# LongLedPcb.net
KiCad netlist of a schematic drawn in Altium Designer
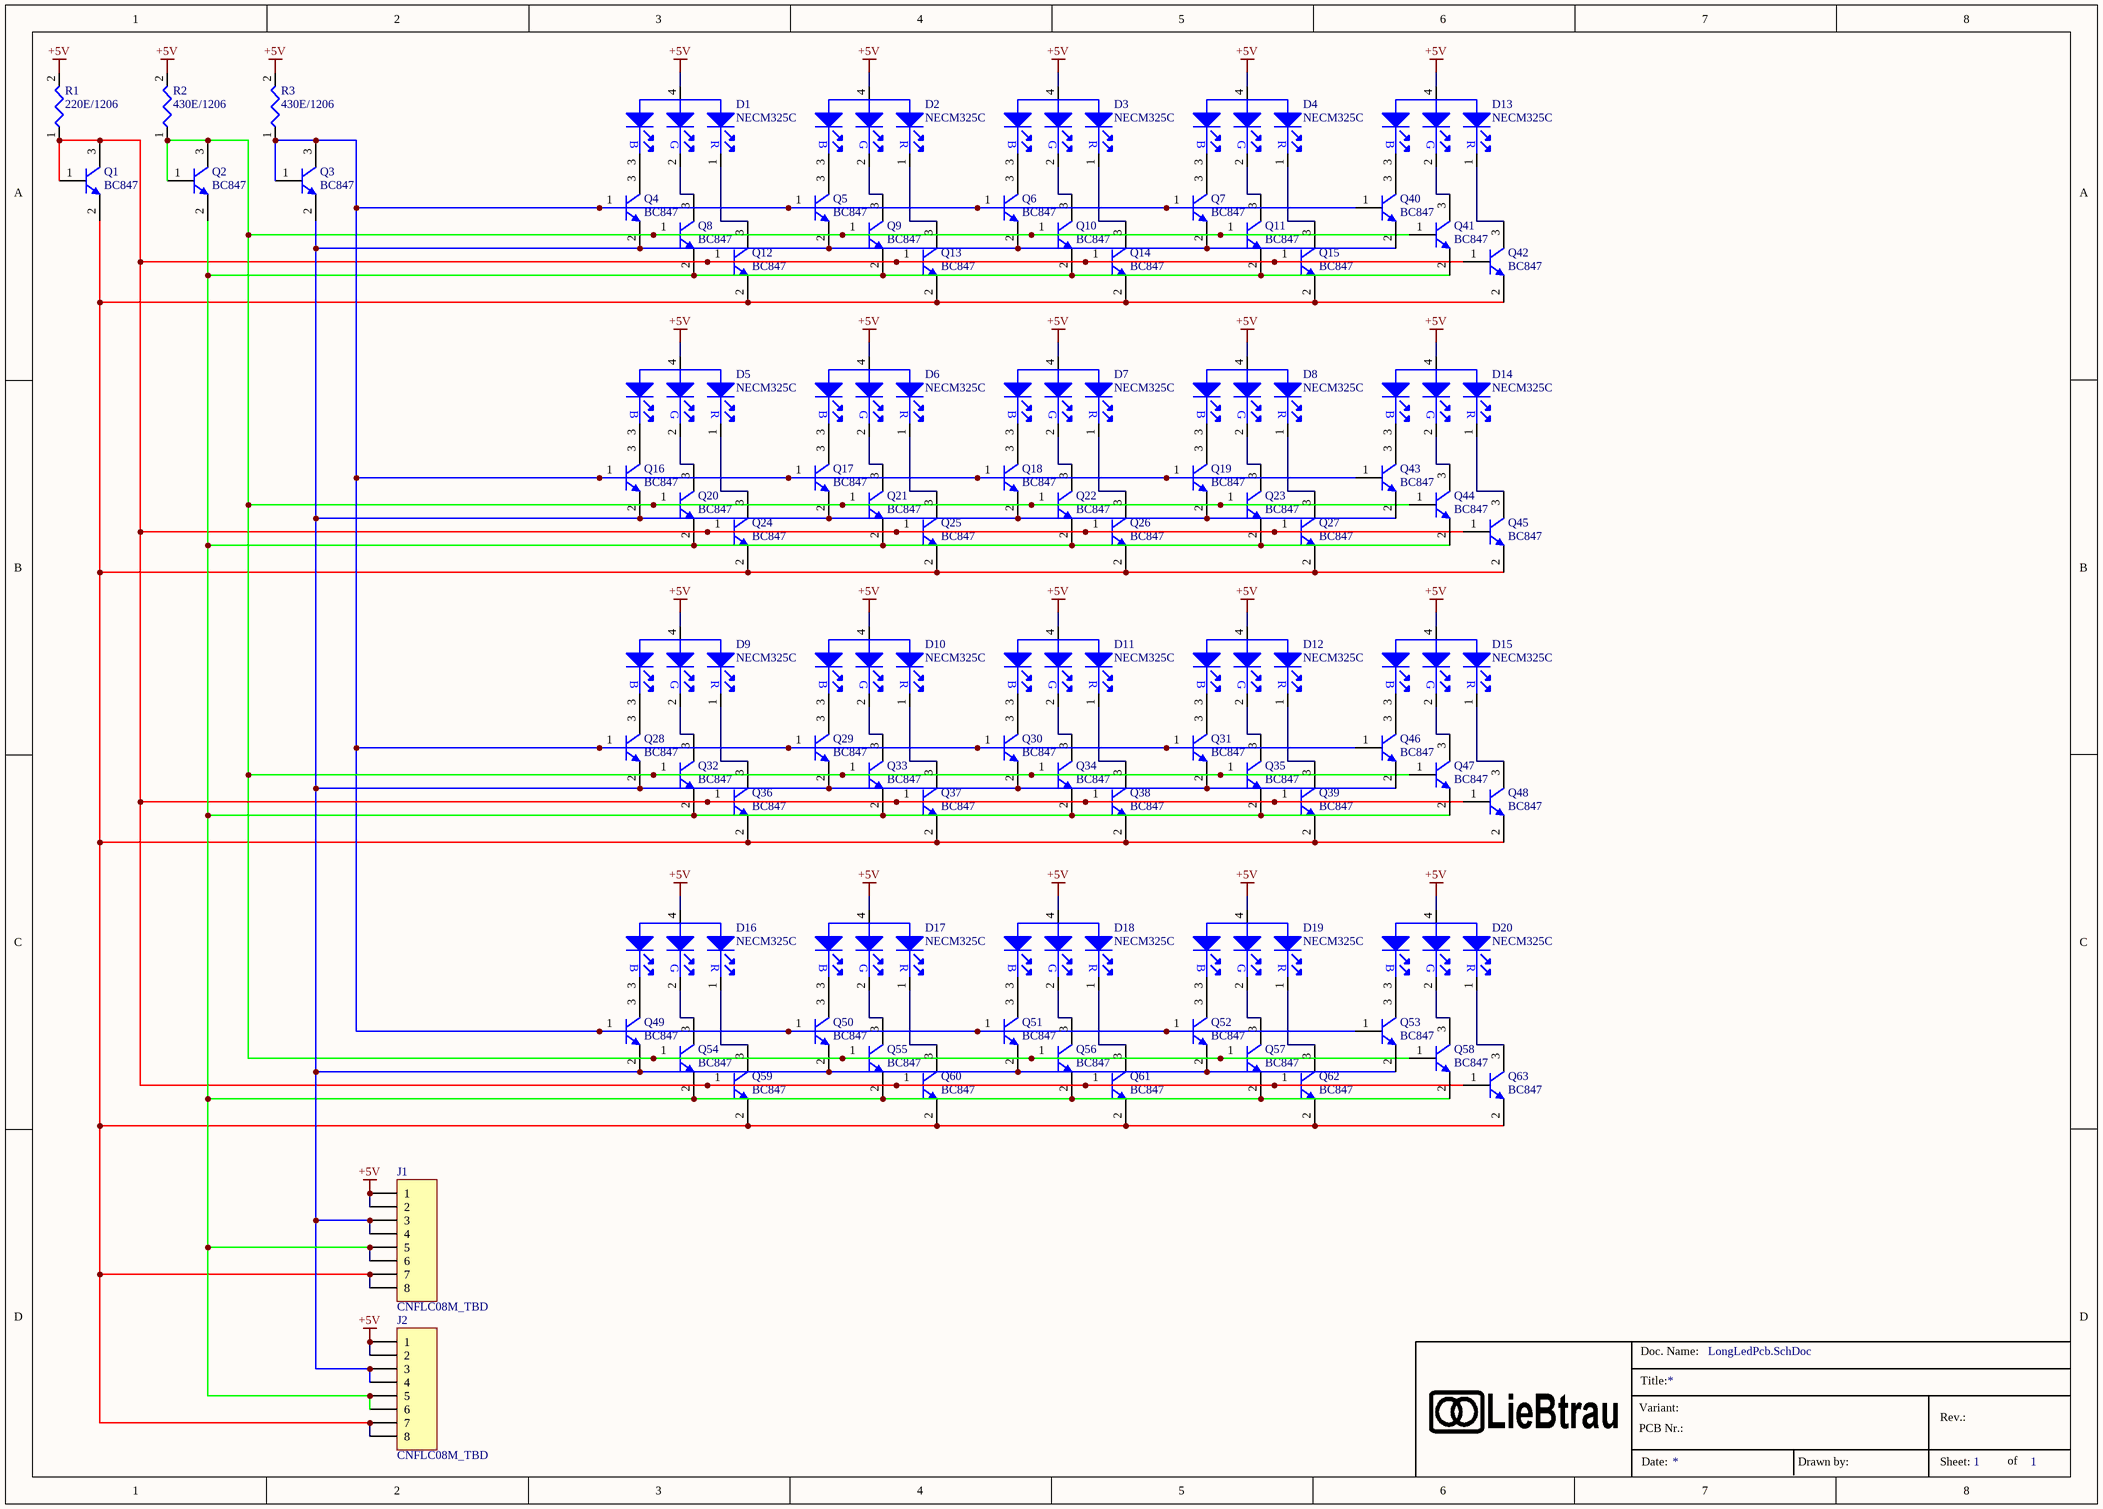
[diagram p0: LongLedPcb.SchDoc]

(export (version "E")
  (design (tool "Eeschema 10.0.6"))
  (components
    (comp (ref "D1")
      (value "NECM325C")
      (footprint "D_PLCC4")
      (fields (field (name "MANUFACTURER") "Nichia"))
      (libsource (lib "Testing") (part "D_LED_RGB"))
    )
    (comp (ref "D2")
      (value "NECM325C")
      (footprint "D_PLCC4")
      (fields (field (name "MANUFACTURER") "Nichia"))
      (libsource (lib "Testing") (part "D_LED_RGB"))
    )
    (comp (ref "D3")
      (value "NECM325C")
      (footprint "D_PLCC4")
      (fields (field (name "MANUFACTURER") "Nichia"))
      (libsource (lib "Testing") (part "D_LED_RGB"))
    )
    (comp (ref "D4")
      (value "NECM325C")
      (footprint "D_PLCC4")
      (fields (field (name "MANUFACTURER") "Nichia"))
      (libsource (lib "Testing") (part "D_LED_RGB"))
    )
    (comp (ref "D5")
      (value "NECM325C")
      (footprint "D_PLCC4")
      (fields (field (name "MANUFACTURER") "Nichia"))
      (libsource (lib "Testing") (part "D_LED_RGB"))
    )
    (comp (ref "D6")
      (value "NECM325C")
      (footprint "D_PLCC4")
      (fields (field (name "MANUFACTURER") "Nichia"))
      (libsource (lib "Testing") (part "D_LED_RGB"))
    )
    (comp (ref "D7")
      (value "NECM325C")
      (footprint "D_PLCC4")
      (fields (field (name "MANUFACTURER") "Nichia"))
      (libsource (lib "Testing") (part "D_LED_RGB"))
    )
    (comp (ref "D8")
      (value "NECM325C")
      (footprint "D_PLCC4")
      (fields (field (name "MANUFACTURER") "Nichia"))
      (libsource (lib "Testing") (part "D_LED_RGB"))
    )
    (comp (ref "D9")
      (value "NECM325C")
      (footprint "D_PLCC4")
      (fields (field (name "MANUFACTURER") "Nichia"))
      (libsource (lib "Testing") (part "D_LED_RGB"))
    )
    (comp (ref "D10")
      (value "NECM325C")
      (footprint "D_PLCC4")
      (fields (field (name "MANUFACTURER") "Nichia"))
      (libsource (lib "Testing") (part "D_LED_RGB"))
    )
    (comp (ref "D11")
      (value "NECM325C")
      (footprint "D_PLCC4")
      (fields (field (name "MANUFACTURER") "Nichia"))
      (libsource (lib "Testing") (part "D_LED_RGB"))
    )
    (comp (ref "D12")
      (value "NECM325C")
      (footprint "D_PLCC4")
      (fields (field (name "MANUFACTURER") "Nichia"))
      (libsource (lib "Testing") (part "D_LED_RGB"))
    )
    (comp (ref "D13")
      (value "NECM325C")
      (footprint "D_PLCC4")
      (fields (field (name "MANUFACTURER") "Nichia"))
      (libsource (lib "Testing") (part "D_LED_RGB"))
    )
    (comp (ref "D14")
      (value "NECM325C")
      (footprint "D_PLCC4")
      (fields (field (name "MANUFACTURER") "Nichia"))
      (libsource (lib "Testing") (part "D_LED_RGB"))
    )
    (comp (ref "D15")
      (value "NECM325C")
      (footprint "D_PLCC4")
      (fields (field (name "MANUFACTURER") "Nichia"))
      (libsource (lib "Testing") (part "D_LED_RGB"))
    )
    (comp (ref "D16")
      (value "NECM325C")
      (footprint "D_PLCC4")
      (fields (field (name "MANUFACTURER") "Nichia"))
      (libsource (lib "Testing") (part "D_LED_RGB"))
    )
    (comp (ref "D17")
      (value "NECM325C")
      (footprint "D_PLCC4")
      (fields (field (name "MANUFACTURER") "Nichia"))
      (libsource (lib "Testing") (part "D_LED_RGB"))
    )
    (comp (ref "D18")
      (value "NECM325C")
      (footprint "D_PLCC4")
      (fields (field (name "MANUFACTURER") "Nichia"))
      (libsource (lib "Testing") (part "D_LED_RGB"))
    )
    (comp (ref "D19")
      (value "NECM325C")
      (footprint "D_PLCC4")
      (fields (field (name "MANUFACTURER") "Nichia"))
      (libsource (lib "Testing") (part "D_LED_RGB"))
    )
    (comp (ref "D20")
      (value "NECM325C")
      (footprint "D_PLCC4")
      (fields (field (name "MANUFACTURER") "Nichia"))
      (libsource (lib "Testing") (part "D_LED_RGB"))
    )
    (comp (ref "J1")
      (value "CNFLC08M_TBD")
      (footprint "J_215079-8")
      (fields (field (name "PART NUMBER") "CNFLC08F_TBD"))
      (libsource (lib "Testing") (part "J_8P"))
    )
    (comp (ref "J2")
      (value "CNFLC08M_TBD")
      (footprint "J_215079-8")
      (fields (field (name "PART NUMBER") "CNFLC08F_TBD"))
      (libsource (lib "Testing") (part "J_8P"))
    )
    (comp (ref "Q1")
      (value "BC847")
      (footprint "SOT23")
      (description "Amplifier Transistor NPN Silicon")
      (libsource (lib "Testing") (part "Q_NPN_1"))
    )
    (comp (ref "Q2")
      (value "BC847")
      (footprint "SOT23")
      (description "Amplifier Transistor NPN Silicon")
      (libsource (lib "Testing") (part "Q_NPN_1"))
    )
    (comp (ref "Q3")
      (value "BC847")
      (footprint "SOT23")
      (description "Amplifier Transistor NPN Silicon")
      (libsource (lib "Testing") (part "Q_NPN_1"))
    )
    (comp (ref "Q4")
      (value "BC847")
      (footprint "SOT23")
      (description "Amplifier Transistor NPN Silicon")
      (libsource (lib "Testing") (part "Q_NPN_1"))
    )
    (comp (ref "Q5")
      (value "BC847")
      (footprint "SOT23")
      (description "Amplifier Transistor NPN Silicon")
      (libsource (lib "Testing") (part "Q_NPN_1"))
    )
    (comp (ref "Q6")
      (value "BC847")
      (footprint "SOT23")
      (description "Amplifier Transistor NPN Silicon")
      (libsource (lib "Testing") (part "Q_NPN_1"))
    )
    (comp (ref "Q7")
      (value "BC847")
      (footprint "SOT23")
      (description "Amplifier Transistor NPN Silicon")
      (libsource (lib "Testing") (part "Q_NPN_1"))
    )
    (comp (ref "Q8")
      (value "BC847")
      (footprint "SOT23")
      (description "Amplifier Transistor NPN Silicon")
      (libsource (lib "Testing") (part "Q_NPN_1"))
    )
    (comp (ref "Q9")
      (value "BC847")
      (footprint "SOT23")
      (description "Amplifier Transistor NPN Silicon")
      (libsource (lib "Testing") (part "Q_NPN_1"))
    )
    (comp (ref "Q10")
      (value "BC847")
      (footprint "SOT23")
      (description "Amplifier Transistor NPN Silicon")
      (libsource (lib "Testing") (part "Q_NPN_1"))
    )
    (comp (ref "Q11")
      (value "BC847")
      (footprint "SOT23")
      (description "Amplifier Transistor NPN Silicon")
      (libsource (lib "Testing") (part "Q_NPN_1"))
    )
    (comp (ref "Q12")
      (value "BC847")
      (footprint "SOT23")
      (description "Amplifier Transistor NPN Silicon")
      (libsource (lib "Testing") (part "Q_NPN_1"))
    )
    (comp (ref "Q13")
      (value "BC847")
      (footprint "SOT23")
      (description "Amplifier Transistor NPN Silicon")
      (libsource (lib "Testing") (part "Q_NPN_1"))
    )
    (comp (ref "Q14")
      (value "BC847")
      (footprint "SOT23")
      (description "Amplifier Transistor NPN Silicon")
      (libsource (lib "Testing") (part "Q_NPN_1"))
    )
    (comp (ref "Q15")
      (value "BC847")
      (footprint "SOT23")
      (description "Amplifier Transistor NPN Silicon")
      (libsource (lib "Testing") (part "Q_NPN_1"))
    )
    (comp (ref "Q16")
      (value "BC847")
      (footprint "SOT23")
      (description "Amplifier Transistor NPN Silicon")
      (libsource (lib "Testing") (part "Q_NPN_1"))
    )
    (comp (ref "Q17")
      (value "BC847")
      (footprint "SOT23")
      (description "Amplifier Transistor NPN Silicon")
      (libsource (lib "Testing") (part "Q_NPN_1"))
    )
    (comp (ref "Q18")
      (value "BC847")
      (footprint "SOT23")
      (description "Amplifier Transistor NPN Silicon")
      (libsource (lib "Testing") (part "Q_NPN_1"))
    )
    (comp (ref "Q19")
      (value "BC847")
      (footprint "SOT23")
      (description "Amplifier Transistor NPN Silicon")
      (libsource (lib "Testing") (part "Q_NPN_1"))
    )
    (comp (ref "Q20")
      (value "BC847")
      (footprint "SOT23")
      (description "Amplifier Transistor NPN Silicon")
      (libsource (lib "Testing") (part "Q_NPN_1"))
    )
    (comp (ref "Q21")
      (value "BC847")
      (footprint "SOT23")
      (description "Amplifier Transistor NPN Silicon")
      (libsource (lib "Testing") (part "Q_NPN_1"))
    )
    (comp (ref "Q22")
      (value "BC847")
      (footprint "SOT23")
      (description "Amplifier Transistor NPN Silicon")
      (libsource (lib "Testing") (part "Q_NPN_1"))
    )
    (comp (ref "Q23")
      (value "BC847")
      (footprint "SOT23")
      (description "Amplifier Transistor NPN Silicon")
      (libsource (lib "Testing") (part "Q_NPN_1"))
    )
    (comp (ref "Q24")
      (value "BC847")
      (footprint "SOT23")
      (description "Amplifier Transistor NPN Silicon")
      (libsource (lib "Testing") (part "Q_NPN_1"))
    )
    (comp (ref "Q25")
      (value "BC847")
      (footprint "SOT23")
      (description "Amplifier Transistor NPN Silicon")
      (libsource (lib "Testing") (part "Q_NPN_1"))
    )
    (comp (ref "Q26")
      (value "BC847")
      (footprint "SOT23")
      (description "Amplifier Transistor NPN Silicon")
      (libsource (lib "Testing") (part "Q_NPN_1"))
    )
    (comp (ref "Q27")
      (value "BC847")
      (footprint "SOT23")
      (description "Amplifier Transistor NPN Silicon")
      (libsource (lib "Testing") (part "Q_NPN_1"))
    )
    (comp (ref "Q28")
      (value "BC847")
      (footprint "SOT23")
      (description "Amplifier Transistor NPN Silicon")
      (libsource (lib "Testing") (part "Q_NPN_1"))
    )
    (comp (ref "Q29")
      (value "BC847")
      (footprint "SOT23")
      (description "Amplifier Transistor NPN Silicon")
      (libsource (lib "Testing") (part "Q_NPN_1"))
    )
    (comp (ref "Q30")
      (value "BC847")
      (footprint "SOT23")
      (description "Amplifier Transistor NPN Silicon")
      (libsource (lib "Testing") (part "Q_NPN_1"))
    )
    (comp (ref "Q31")
      (value "BC847")
      (footprint "SOT23")
      (description "Amplifier Transistor NPN Silicon")
      (libsource (lib "Testing") (part "Q_NPN_1"))
    )
    (comp (ref "Q32")
      (value "BC847")
      (footprint "SOT23")
      (description "Amplifier Transistor NPN Silicon")
      (libsource (lib "Testing") (part "Q_NPN_1"))
    )
    (comp (ref "Q33")
      (value "BC847")
      (footprint "SOT23")
      (description "Amplifier Transistor NPN Silicon")
      (libsource (lib "Testing") (part "Q_NPN_1"))
    )
    (comp (ref "Q34")
      (value "BC847")
      (footprint "SOT23")
      (description "Amplifier Transistor NPN Silicon")
      (libsource (lib "Testing") (part "Q_NPN_1"))
    )
    (comp (ref "Q35")
      (value "BC847")
      (footprint "SOT23")
      (description "Amplifier Transistor NPN Silicon")
      (libsource (lib "Testing") (part "Q_NPN_1"))
    )
    (comp (ref "Q36")
      (value "BC847")
      (footprint "SOT23")
      (description "Amplifier Transistor NPN Silicon")
      (libsource (lib "Testing") (part "Q_NPN_1"))
    )
    (comp (ref "Q37")
      (value "BC847")
      (footprint "SOT23")
      (description "Amplifier Transistor NPN Silicon")
      (libsource (lib "Testing") (part "Q_NPN_1"))
    )
    (comp (ref "Q38")
      (value "BC847")
      (footprint "SOT23")
      (description "Amplifier Transistor NPN Silicon")
      (libsource (lib "Testing") (part "Q_NPN_1"))
    )
    (comp (ref "Q39")
      (value "BC847")
      (footprint "SOT23")
      (description "Amplifier Transistor NPN Silicon")
      (libsource (lib "Testing") (part "Q_NPN_1"))
    )
    (comp (ref "Q40")
      (value "BC847")
      (footprint "SOT23")
      (description "Amplifier Transistor NPN Silicon")
      (libsource (lib "Testing") (part "Q_NPN_1"))
    )
    (comp (ref "Q41")
      (value "BC847")
      (footprint "SOT23")
      (description "Amplifier Transistor NPN Silicon")
      (libsource (lib "Testing") (part "Q_NPN_1"))
    )
    (comp (ref "Q42")
      (value "BC847")
      (footprint "SOT23")
      (description "Amplifier Transistor NPN Silicon")
      (libsource (lib "Testing") (part "Q_NPN_1"))
    )
    (comp (ref "Q43")
      (value "BC847")
      (footprint "SOT23")
      (description "Amplifier Transistor NPN Silicon")
      (libsource (lib "Testing") (part "Q_NPN_1"))
    )
    (comp (ref "Q44")
      (value "BC847")
      (footprint "SOT23")
      (description "Amplifier Transistor NPN Silicon")
      (libsource (lib "Testing") (part "Q_NPN_1"))
    )
    (comp (ref "Q45")
      (value "BC847")
      (footprint "SOT23")
      (description "Amplifier Transistor NPN Silicon")
      (libsource (lib "Testing") (part "Q_NPN_1"))
    )
    (comp (ref "Q46")
      (value "BC847")
      (footprint "SOT23")
      (description "Amplifier Transistor NPN Silicon")
      (libsource (lib "Testing") (part "Q_NPN_1"))
    )
    (comp (ref "Q47")
      (value "BC847")
      (footprint "SOT23")
      (description "Amplifier Transistor NPN Silicon")
      (libsource (lib "Testing") (part "Q_NPN_1"))
    )
    (comp (ref "Q48")
      (value "BC847")
      (footprint "SOT23")
      (description "Amplifier Transistor NPN Silicon")
      (libsource (lib "Testing") (part "Q_NPN_1"))
    )
    (comp (ref "Q49")
      (value "BC847")
      (footprint "SOT23")
      (description "Amplifier Transistor NPN Silicon")
      (libsource (lib "Testing") (part "Q_NPN_1"))
    )
    (comp (ref "Q50")
      (value "BC847")
      (footprint "SOT23")
      (description "Amplifier Transistor NPN Silicon")
      (libsource (lib "Testing") (part "Q_NPN_1"))
    )
    (comp (ref "Q51")
      (value "BC847")
      (footprint "SOT23")
      (description "Amplifier Transistor NPN Silicon")
      (libsource (lib "Testing") (part "Q_NPN_1"))
    )
    (comp (ref "Q52")
      (value "BC847")
      (footprint "SOT23")
      (description "Amplifier Transistor NPN Silicon")
      (libsource (lib "Testing") (part "Q_NPN_1"))
    )
    (comp (ref "Q53")
      (value "BC847")
      (footprint "SOT23")
      (description "Amplifier Transistor NPN Silicon")
      (libsource (lib "Testing") (part "Q_NPN_1"))
    )
    (comp (ref "Q54")
      (value "BC847")
      (footprint "SOT23")
      (description "Amplifier Transistor NPN Silicon")
      (libsource (lib "Testing") (part "Q_NPN_1"))
    )
    (comp (ref "Q55")
      (value "BC847")
      (footprint "SOT23")
      (description "Amplifier Transistor NPN Silicon")
      (libsource (lib "Testing") (part "Q_NPN_1"))
    )
    (comp (ref "Q56")
      (value "BC847")
      (footprint "SOT23")
      (description "Amplifier Transistor NPN Silicon")
      (libsource (lib "Testing") (part "Q_NPN_1"))
    )
    (comp (ref "Q57")
      (value "BC847")
      (footprint "SOT23")
      (description "Amplifier Transistor NPN Silicon")
      (libsource (lib "Testing") (part "Q_NPN_1"))
    )
    (comp (ref "Q58")
      (value "BC847")
      (footprint "SOT23")
      (description "Amplifier Transistor NPN Silicon")
      (libsource (lib "Testing") (part "Q_NPN_1"))
    )
    (comp (ref "Q59")
      (value "BC847")
      (footprint "SOT23")
      (description "Amplifier Transistor NPN Silicon")
      (libsource (lib "Testing") (part "Q_NPN_1"))
    )
    (comp (ref "Q60")
      (value "BC847")
      (footprint "SOT23")
      (description "Amplifier Transistor NPN Silicon")
      (libsource (lib "Testing") (part "Q_NPN_1"))
    )
    (comp (ref "Q61")
      (value "BC847")
      (footprint "SOT23")
      (description "Amplifier Transistor NPN Silicon")
      (libsource (lib "Testing") (part "Q_NPN_1"))
    )
    (comp (ref "Q62")
      (value "BC847")
      (footprint "SOT23")
      (description "Amplifier Transistor NPN Silicon")
      (libsource (lib "Testing") (part "Q_NPN_1"))
    )
    (comp (ref "Q63")
      (value "BC847")
      (footprint "SOT23")
      (description "Amplifier Transistor NPN Silicon")
      (libsource (lib "Testing") (part "Q_NPN_1"))
    )
    (comp (ref "R1")
      (value "220E/1206")
      (footprint "R_1206")
      (description "Resistor")
      (fields (field (name "PART NUMBER") "YRES220_1206") (field (name "MANUFACTURER") "Yageo (Phycomp)"))
      (libsource (lib "Testing") (part "R_RES"))
    )
    (comp (ref "R2")
      (value "430E/1206")
      (footprint "R_1206")
      (description "Resistor")
      (fields (field (name "PART NUMBER") "YRES430E_TBD") (field (name "MANUFACTURER") "Welwyn"))
      (libsource (lib "Testing") (part "R_RES"))
    )
    (comp (ref "R3")
      (value "430E/1206")
      (footprint "R_1206")
      (description "Resistor")
      (fields (field (name "PART NUMBER") "YRES430E_TBD") (field (name "MANUFACTURER") "Welwyn"))
      (libsource (lib "Testing") (part "R_RES"))
    )
  )
  (nets
    (net (code "1") (name "+5V") (class "Default")
      (node (ref "D1") (pin "4") (pinfunction "A_4") (pintype "passive"))
      (node (ref "D10") (pin "4") (pinfunction "A_4") (pintype "passive"))
      (node (ref "D11") (pin "4") (pinfunction "A_4") (pintype "passive"))
      (node (ref "D12") (pin "4") (pinfunction "A_4") (pintype "passive"))
      (node (ref "D13") (pin "4") (pinfunction "A_4") (pintype "passive"))
      (node (ref "D14") (pin "4") (pinfunction "A_4") (pintype "passive"))
      (node (ref "D15") (pin "4") (pinfunction "A_4") (pintype "passive"))
      (node (ref "D16") (pin "4") (pinfunction "A_4") (pintype "passive"))
      (node (ref "D17") (pin "4") (pinfunction "A_4") (pintype "passive"))
      (node (ref "D18") (pin "4") (pinfunction "A_4") (pintype "passive"))
      (node (ref "D19") (pin "4") (pinfunction "A_4") (pintype "passive"))
      (node (ref "D2") (pin "4") (pinfunction "A_4") (pintype "passive"))
      (node (ref "D20") (pin "4") (pinfunction "A_4") (pintype "passive"))
      (node (ref "D3") (pin "4") (pinfunction "A_4") (pintype "passive"))
      (node (ref "D4") (pin "4") (pinfunction "A_4") (pintype "passive"))
      (node (ref "D5") (pin "4") (pinfunction "A_4") (pintype "passive"))
      (node (ref "D6") (pin "4") (pinfunction "A_4") (pintype "passive"))
      (node (ref "D7") (pin "4") (pinfunction "A_4") (pintype "passive"))
      (node (ref "D8") (pin "4") (pinfunction "A_4") (pintype "passive"))
      (node (ref "D9") (pin "4") (pinfunction "A_4") (pintype "passive"))
      (node (ref "J1") (pin "1") (pinfunction "1_1") (pintype "passive"))
      (node (ref "J1") (pin "2") (pinfunction "2_2") (pintype "passive"))
      (node (ref "J2") (pin "1") (pinfunction "1_1") (pintype "passive"))
      (node (ref "J2") (pin "2") (pinfunction "2_2") (pintype "passive"))
      (node (ref "R1") (pin "2") (pinfunction "2_2") (pintype "passive"))
      (node (ref "R2") (pin "2") (pinfunction "2_2") (pintype "passive"))
      (node (ref "R3") (pin "2") (pinfunction "2_2") (pintype "passive"))
    )
    (net (code "2") (name "Net-(Q1-B)") (class "Default")
      (node (ref "J1") (pin "7") (pinfunction "7_7") (pintype "passive"))
      (node (ref "J1") (pin "8") (pinfunction "8_8") (pintype "passive"))
      (node (ref "J2") (pin "7") (pinfunction "7_7") (pintype "passive"))
      (node (ref "J2") (pin "8") (pinfunction "8_8") (pintype "passive"))
      (node (ref "Q1") (pin "2") (pinfunction "B_2") (pintype "passive"))
      (node (ref "Q12") (pin "2") (pinfunction "B_2") (pintype "passive"))
      (node (ref "Q13") (pin "2") (pinfunction "B_2") (pintype "passive"))
      (node (ref "Q14") (pin "2") (pinfunction "B_2") (pintype "passive"))
      (node (ref "Q15") (pin "2") (pinfunction "B_2") (pintype "passive"))
      (node (ref "Q24") (pin "2") (pinfunction "B_2") (pintype "passive"))
      (node (ref "Q25") (pin "2") (pinfunction "B_2") (pintype "passive"))
      (node (ref "Q26") (pin "2") (pinfunction "B_2") (pintype "passive"))
      (node (ref "Q27") (pin "2") (pinfunction "B_2") (pintype "passive"))
      (node (ref "Q36") (pin "2") (pinfunction "B_2") (pintype "passive"))
      (node (ref "Q37") (pin "2") (pinfunction "B_2") (pintype "passive"))
      (node (ref "Q38") (pin "2") (pinfunction "B_2") (pintype "passive"))
      (node (ref "Q39") (pin "2") (pinfunction "B_2") (pintype "passive"))
      (node (ref "Q42") (pin "2") (pinfunction "B_2") (pintype "passive"))
      (node (ref "Q45") (pin "2") (pinfunction "B_2") (pintype "passive"))
      (node (ref "Q48") (pin "2") (pinfunction "B_2") (pintype "passive"))
      (node (ref "Q59") (pin "2") (pinfunction "B_2") (pintype "passive"))
      (node (ref "Q60") (pin "2") (pinfunction "B_2") (pintype "passive"))
      (node (ref "Q61") (pin "2") (pinfunction "B_2") (pintype "passive"))
      (node (ref "Q62") (pin "2") (pinfunction "B_2") (pintype "passive"))
      (node (ref "Q63") (pin "2") (pinfunction "B_2") (pintype "passive"))
    )
    (net (code "3") (name "Net-(Q1-C)") (class "Default")
      (node (ref "Q1") (pin "1") (pinfunction "C_1") (pintype "passive"))
      (node (ref "Q1") (pin "3") (pinfunction "E_3") (pintype "passive"))
      (node (ref "Q12") (pin "1") (pinfunction "C_1") (pintype "passive"))
      (node (ref "Q13") (pin "1") (pinfunction "C_1") (pintype "passive"))
      (node (ref "Q14") (pin "1") (pinfunction "C_1") (pintype "passive"))
      (node (ref "Q15") (pin "1") (pinfunction "C_1") (pintype "passive"))
      (node (ref "Q24") (pin "1") (pinfunction "C_1") (pintype "passive"))
      (node (ref "Q25") (pin "1") (pinfunction "C_1") (pintype "passive"))
      (node (ref "Q26") (pin "1") (pinfunction "C_1") (pintype "passive"))
      (node (ref "Q27") (pin "1") (pinfunction "C_1") (pintype "passive"))
      (node (ref "Q36") (pin "1") (pinfunction "C_1") (pintype "passive"))
      (node (ref "Q37") (pin "1") (pinfunction "C_1") (pintype "passive"))
      (node (ref "Q38") (pin "1") (pinfunction "C_1") (pintype "passive"))
      (node (ref "Q39") (pin "1") (pinfunction "C_1") (pintype "passive"))
      (node (ref "Q42") (pin "1") (pinfunction "C_1") (pintype "passive"))
      (node (ref "Q45") (pin "1") (pinfunction "C_1") (pintype "passive"))
      (node (ref "Q48") (pin "1") (pinfunction "C_1") (pintype "passive"))
      (node (ref "Q59") (pin "1") (pinfunction "C_1") (pintype "passive"))
      (node (ref "Q60") (pin "1") (pinfunction "C_1") (pintype "passive"))
      (node (ref "Q61") (pin "1") (pinfunction "C_1") (pintype "passive"))
      (node (ref "Q62") (pin "1") (pinfunction "C_1") (pintype "passive"))
      (node (ref "Q63") (pin "1") (pinfunction "C_1") (pintype "passive"))
      (node (ref "R1") (pin "1") (pinfunction "1_1") (pintype "passive"))
    )
    (net (code "4") (name "Net-(Q4-E)") (class "Default")
      (node (ref "D1") (pin "3") (pinfunction "C_3") (pintype "passive"))
      (node (ref "Q4") (pin "3") (pinfunction "E_3") (pintype "passive"))
    )
    (net (code "5") (name "Net-(Q5-E)") (class "Default")
      (node (ref "D2") (pin "3") (pinfunction "C_3") (pintype "passive"))
      (node (ref "Q5") (pin "3") (pinfunction "E_3") (pintype "passive"))
    )
    (net (code "6") (name "Net-(Q6-E)") (class "Default")
      (node (ref "D3") (pin "3") (pinfunction "C_3") (pintype "passive"))
      (node (ref "Q6") (pin "3") (pinfunction "E_3") (pintype "passive"))
    )
    (net (code "7") (name "Net-(Q7-E)") (class "Default")
      (node (ref "D4") (pin "3") (pinfunction "C_3") (pintype "passive"))
      (node (ref "Q7") (pin "3") (pinfunction "E_3") (pintype "passive"))
    )
    (net (code "8") (name "Net-(Q8-E)") (class "Default")
      (node (ref "D1") (pin "2") (pinfunction "C_2") (pintype "passive"))
      (node (ref "Q8") (pin "3") (pinfunction "E_3") (pintype "passive"))
    )
    (net (code "9") (name "Net-(Q9-E)") (class "Default")
      (node (ref "D2") (pin "2") (pinfunction "C_2") (pintype "passive"))
      (node (ref "Q9") (pin "3") (pinfunction "E_3") (pintype "passive"))
    )
    (net (code "10") (name "Net-(Q10-B)") (class "Default")
      (node (ref "J1") (pin "5") (pinfunction "5_5") (pintype "passive"))
      (node (ref "J1") (pin "6") (pinfunction "6_6") (pintype "passive"))
      (node (ref "J2") (pin "5") (pinfunction "5_5") (pintype "passive"))
      (node (ref "J2") (pin "6") (pinfunction "6_6") (pintype "passive"))
      (node (ref "Q10") (pin "2") (pinfunction "B_2") (pintype "passive"))
      (node (ref "Q11") (pin "2") (pinfunction "B_2") (pintype "passive"))
      (node (ref "Q2") (pin "2") (pinfunction "B_2") (pintype "passive"))
      (node (ref "Q20") (pin "2") (pinfunction "B_2") (pintype "passive"))
      (node (ref "Q21") (pin "2") (pinfunction "B_2") (pintype "passive"))
      (node (ref "Q22") (pin "2") (pinfunction "B_2") (pintype "passive"))
      (node (ref "Q23") (pin "2") (pinfunction "B_2") (pintype "passive"))
      (node (ref "Q32") (pin "2") (pinfunction "B_2") (pintype "passive"))
      (node (ref "Q33") (pin "2") (pinfunction "B_2") (pintype "passive"))
      (node (ref "Q34") (pin "2") (pinfunction "B_2") (pintype "passive"))
      (node (ref "Q35") (pin "2") (pinfunction "B_2") (pintype "passive"))
      (node (ref "Q41") (pin "2") (pinfunction "B_2") (pintype "passive"))
      (node (ref "Q44") (pin "2") (pinfunction "B_2") (pintype "passive"))
      (node (ref "Q47") (pin "2") (pinfunction "B_2") (pintype "passive"))
      (node (ref "Q54") (pin "2") (pinfunction "B_2") (pintype "passive"))
      (node (ref "Q55") (pin "2") (pinfunction "B_2") (pintype "passive"))
      (node (ref "Q56") (pin "2") (pinfunction "B_2") (pintype "passive"))
      (node (ref "Q57") (pin "2") (pinfunction "B_2") (pintype "passive"))
      (node (ref "Q58") (pin "2") (pinfunction "B_2") (pintype "passive"))
      (node (ref "Q8") (pin "2") (pinfunction "B_2") (pintype "passive"))
      (node (ref "Q9") (pin "2") (pinfunction "B_2") (pintype "passive"))
    )
    (net (code "11") (name "Net-(Q10-C)") (class "Default")
      (node (ref "Q10") (pin "1") (pinfunction "C_1") (pintype "passive"))
      (node (ref "Q11") (pin "1") (pinfunction "C_1") (pintype "passive"))
      (node (ref "Q2") (pin "1") (pinfunction "C_1") (pintype "passive"))
      (node (ref "Q2") (pin "3") (pinfunction "E_3") (pintype "passive"))
      (node (ref "Q20") (pin "1") (pinfunction "C_1") (pintype "passive"))
      (node (ref "Q21") (pin "1") (pinfunction "C_1") (pintype "passive"))
      (node (ref "Q22") (pin "1") (pinfunction "C_1") (pintype "passive"))
      (node (ref "Q23") (pin "1") (pinfunction "C_1") (pintype "passive"))
      (node (ref "Q32") (pin "1") (pinfunction "C_1") (pintype "passive"))
      (node (ref "Q33") (pin "1") (pinfunction "C_1") (pintype "passive"))
      (node (ref "Q34") (pin "1") (pinfunction "C_1") (pintype "passive"))
      (node (ref "Q35") (pin "1") (pinfunction "C_1") (pintype "passive"))
      (node (ref "Q41") (pin "1") (pinfunction "C_1") (pintype "passive"))
      (node (ref "Q44") (pin "1") (pinfunction "C_1") (pintype "passive"))
      (node (ref "Q47") (pin "1") (pinfunction "C_1") (pintype "passive"))
      (node (ref "Q54") (pin "1") (pinfunction "C_1") (pintype "passive"))
      (node (ref "Q55") (pin "1") (pinfunction "C_1") (pintype "passive"))
      (node (ref "Q56") (pin "1") (pinfunction "C_1") (pintype "passive"))
      (node (ref "Q57") (pin "1") (pinfunction "C_1") (pintype "passive"))
      (node (ref "Q58") (pin "1") (pinfunction "C_1") (pintype "passive"))
      (node (ref "Q8") (pin "1") (pinfunction "C_1") (pintype "passive"))
      (node (ref "Q9") (pin "1") (pinfunction "C_1") (pintype "passive"))
      (node (ref "R2") (pin "1") (pinfunction "1_1") (pintype "passive"))
    )
    (net (code "12") (name "Net-(Q10-E)") (class "Default")
      (node (ref "D3") (pin "2") (pinfunction "C_2") (pintype "passive"))
      (node (ref "Q10") (pin "3") (pinfunction "E_3") (pintype "passive"))
    )
    (net (code "13") (name "Net-(Q11-E)") (class "Default")
      (node (ref "D4") (pin "2") (pinfunction "C_2") (pintype "passive"))
      (node (ref "Q11") (pin "3") (pinfunction "E_3") (pintype "passive"))
    )
    (net (code "14") (name "Net-(Q12-E)") (class "Default")
      (node (ref "D1") (pin "1") (pinfunction "C_1") (pintype "passive"))
      (node (ref "Q12") (pin "3") (pinfunction "E_3") (pintype "passive"))
    )
    (net (code "15") (name "Net-(Q13-E)") (class "Default")
      (node (ref "D2") (pin "1") (pinfunction "C_1") (pintype "passive"))
      (node (ref "Q13") (pin "3") (pinfunction "E_3") (pintype "passive"))
    )
    (net (code "16") (name "Net-(Q14-E)") (class "Default")
      (node (ref "D3") (pin "1") (pinfunction "C_1") (pintype "passive"))
      (node (ref "Q14") (pin "3") (pinfunction "E_3") (pintype "passive"))
    )
    (net (code "17") (name "Net-(Q15-E)") (class "Default")
      (node (ref "D4") (pin "1") (pinfunction "C_1") (pintype "passive"))
      (node (ref "Q15") (pin "3") (pinfunction "E_3") (pintype "passive"))
    )
    (net (code "18") (name "Net-(Q16-B)") (class "Default")
      (node (ref "J1") (pin "3") (pinfunction "3_3") (pintype "passive"))
      (node (ref "J1") (pin "4") (pinfunction "4_4") (pintype "passive"))
      (node (ref "J2") (pin "3") (pinfunction "3_3") (pintype "passive"))
      (node (ref "J2") (pin "4") (pinfunction "4_4") (pintype "passive"))
      (node (ref "Q16") (pin "2") (pinfunction "B_2") (pintype "passive"))
      (node (ref "Q17") (pin "2") (pinfunction "B_2") (pintype "passive"))
      (node (ref "Q18") (pin "2") (pinfunction "B_2") (pintype "passive"))
      (node (ref "Q19") (pin "2") (pinfunction "B_2") (pintype "passive"))
      (node (ref "Q28") (pin "2") (pinfunction "B_2") (pintype "passive"))
      (node (ref "Q29") (pin "2") (pinfunction "B_2") (pintype "passive"))
      (node (ref "Q3") (pin "2") (pinfunction "B_2") (pintype "passive"))
      (node (ref "Q30") (pin "2") (pinfunction "B_2") (pintype "passive"))
      (node (ref "Q31") (pin "2") (pinfunction "B_2") (pintype "passive"))
      (node (ref "Q4") (pin "2") (pinfunction "B_2") (pintype "passive"))
      (node (ref "Q40") (pin "2") (pinfunction "B_2") (pintype "passive"))
      (node (ref "Q43") (pin "2") (pinfunction "B_2") (pintype "passive"))
      (node (ref "Q46") (pin "2") (pinfunction "B_2") (pintype "passive"))
      (node (ref "Q49") (pin "2") (pinfunction "B_2") (pintype "passive"))
      (node (ref "Q5") (pin "2") (pinfunction "B_2") (pintype "passive"))
      (node (ref "Q50") (pin "2") (pinfunction "B_2") (pintype "passive"))
      (node (ref "Q51") (pin "2") (pinfunction "B_2") (pintype "passive"))
      (node (ref "Q52") (pin "2") (pinfunction "B_2") (pintype "passive"))
      (node (ref "Q53") (pin "2") (pinfunction "B_2") (pintype "passive"))
      (node (ref "Q6") (pin "2") (pinfunction "B_2") (pintype "passive"))
      (node (ref "Q7") (pin "2") (pinfunction "B_2") (pintype "passive"))
    )
    (net (code "19") (name "Net-(Q16-C)") (class "Default")
      (node (ref "Q16") (pin "1") (pinfunction "C_1") (pintype "passive"))
      (node (ref "Q17") (pin "1") (pinfunction "C_1") (pintype "passive"))
      (node (ref "Q18") (pin "1") (pinfunction "C_1") (pintype "passive"))
      (node (ref "Q19") (pin "1") (pinfunction "C_1") (pintype "passive"))
      (node (ref "Q28") (pin "1") (pinfunction "C_1") (pintype "passive"))
      (node (ref "Q29") (pin "1") (pinfunction "C_1") (pintype "passive"))
      (node (ref "Q3") (pin "1") (pinfunction "C_1") (pintype "passive"))
      (node (ref "Q3") (pin "3") (pinfunction "E_3") (pintype "passive"))
      (node (ref "Q30") (pin "1") (pinfunction "C_1") (pintype "passive"))
      (node (ref "Q31") (pin "1") (pinfunction "C_1") (pintype "passive"))
      (node (ref "Q4") (pin "1") (pinfunction "C_1") (pintype "passive"))
      (node (ref "Q40") (pin "1") (pinfunction "C_1") (pintype "passive"))
      (node (ref "Q43") (pin "1") (pinfunction "C_1") (pintype "passive"))
      (node (ref "Q46") (pin "1") (pinfunction "C_1") (pintype "passive"))
      (node (ref "Q49") (pin "1") (pinfunction "C_1") (pintype "passive"))
      (node (ref "Q5") (pin "1") (pinfunction "C_1") (pintype "passive"))
      (node (ref "Q50") (pin "1") (pinfunction "C_1") (pintype "passive"))
      (node (ref "Q51") (pin "1") (pinfunction "C_1") (pintype "passive"))
      (node (ref "Q52") (pin "1") (pinfunction "C_1") (pintype "passive"))
      (node (ref "Q53") (pin "1") (pinfunction "C_1") (pintype "passive"))
      (node (ref "Q6") (pin "1") (pinfunction "C_1") (pintype "passive"))
      (node (ref "Q7") (pin "1") (pinfunction "C_1") (pintype "passive"))
      (node (ref "R3") (pin "1") (pinfunction "1_1") (pintype "passive"))
    )
    (net (code "20") (name "Net-(Q16-E)") (class "Default")
      (node (ref "D5") (pin "3") (pinfunction "C_3") (pintype "passive"))
      (node (ref "Q16") (pin "3") (pinfunction "E_3") (pintype "passive"))
    )
    (net (code "21") (name "Net-(Q17-E)") (class "Default")
      (node (ref "D6") (pin "3") (pinfunction "C_3") (pintype "passive"))
      (node (ref "Q17") (pin "3") (pinfunction "E_3") (pintype "passive"))
    )
    (net (code "22") (name "Net-(Q18-E)") (class "Default")
      (node (ref "D7") (pin "3") (pinfunction "C_3") (pintype "passive"))
      (node (ref "Q18") (pin "3") (pinfunction "E_3") (pintype "passive"))
    )
    (net (code "23") (name "Net-(Q19-E)") (class "Default")
      (node (ref "D8") (pin "3") (pinfunction "C_3") (pintype "passive"))
      (node (ref "Q19") (pin "3") (pinfunction "E_3") (pintype "passive"))
    )
    (net (code "24") (name "Net-(Q20-E)") (class "Default")
      (node (ref "D5") (pin "2") (pinfunction "C_2") (pintype "passive"))
      (node (ref "Q20") (pin "3") (pinfunction "E_3") (pintype "passive"))
    )
    (net (code "25") (name "Net-(Q21-E)") (class "Default")
      (node (ref "D6") (pin "2") (pinfunction "C_2") (pintype "passive"))
      (node (ref "Q21") (pin "3") (pinfunction "E_3") (pintype "passive"))
    )
    (net (code "26") (name "Net-(Q22-E)") (class "Default")
      (node (ref "D7") (pin "2") (pinfunction "C_2") (pintype "passive"))
      (node (ref "Q22") (pin "3") (pinfunction "E_3") (pintype "passive"))
    )
    (net (code "27") (name "Net-(Q23-E)") (class "Default")
      (node (ref "D8") (pin "2") (pinfunction "C_2") (pintype "passive"))
      (node (ref "Q23") (pin "3") (pinfunction "E_3") (pintype "passive"))
    )
    (net (code "28") (name "Net-(Q24-E)") (class "Default")
      (node (ref "D5") (pin "1") (pinfunction "C_1") (pintype "passive"))
      (node (ref "Q24") (pin "3") (pinfunction "E_3") (pintype "passive"))
    )
    (net (code "29") (name "Net-(Q25-E)") (class "Default")
      (node (ref "D6") (pin "1") (pinfunction "C_1") (pintype "passive"))
      (node (ref "Q25") (pin "3") (pinfunction "E_3") (pintype "passive"))
    )
    (net (code "30") (name "Net-(Q26-E)") (class "Default")
      (node (ref "D7") (pin "1") (pinfunction "C_1") (pintype "passive"))
      (node (ref "Q26") (pin "3") (pinfunction "E_3") (pintype "passive"))
    )
    (net (code "31") (name "Net-(Q27-E)") (class "Default")
      (node (ref "D8") (pin "1") (pinfunction "C_1") (pintype "passive"))
      (node (ref "Q27") (pin "3") (pinfunction "E_3") (pintype "passive"))
    )
    (net (code "32") (name "Net-(Q28-E)") (class "Default")
      (node (ref "D9") (pin "3") (pinfunction "C_3") (pintype "passive"))
      (node (ref "Q28") (pin "3") (pinfunction "E_3") (pintype "passive"))
    )
    (net (code "33") (name "Net-(Q29-E)") (class "Default")
      (node (ref "D10") (pin "3") (pinfunction "C_3") (pintype "passive"))
      (node (ref "Q29") (pin "3") (pinfunction "E_3") (pintype "passive"))
    )
    (net (code "34") (name "Net-(Q30-E)") (class "Default")
      (node (ref "D11") (pin "3") (pinfunction "C_3") (pintype "passive"))
      (node (ref "Q30") (pin "3") (pinfunction "E_3") (pintype "passive"))
    )
    (net (code "35") (name "Net-(Q31-E)") (class "Default")
      (node (ref "D12") (pin "3") (pinfunction "C_3") (pintype "passive"))
      (node (ref "Q31") (pin "3") (pinfunction "E_3") (pintype "passive"))
    )
    (net (code "36") (name "Net-(Q32-E)") (class "Default")
      (node (ref "D9") (pin "2") (pinfunction "C_2") (pintype "passive"))
      (node (ref "Q32") (pin "3") (pinfunction "E_3") (pintype "passive"))
    )
    (net (code "37") (name "Net-(Q33-E)") (class "Default")
      (node (ref "D10") (pin "2") (pinfunction "C_2") (pintype "passive"))
      (node (ref "Q33") (pin "3") (pinfunction "E_3") (pintype "passive"))
    )
    (net (code "38") (name "Net-(Q34-E)") (class "Default")
      (node (ref "D11") (pin "2") (pinfunction "C_2") (pintype "passive"))
      (node (ref "Q34") (pin "3") (pinfunction "E_3") (pintype "passive"))
    )
    (net (code "39") (name "Net-(Q35-E)") (class "Default")
      (node (ref "D12") (pin "2") (pinfunction "C_2") (pintype "passive"))
      (node (ref "Q35") (pin "3") (pinfunction "E_3") (pintype "passive"))
    )
    (net (code "40") (name "Net-(Q36-E)") (class "Default")
      (node (ref "D9") (pin "1") (pinfunction "C_1") (pintype "passive"))
      (node (ref "Q36") (pin "3") (pinfunction "E_3") (pintype "passive"))
    )
    (net (code "41") (name "Net-(Q37-E)") (class "Default")
      (node (ref "D10") (pin "1") (pinfunction "C_1") (pintype "passive"))
      (node (ref "Q37") (pin "3") (pinfunction "E_3") (pintype "passive"))
    )
    (net (code "42") (name "Net-(Q38-E)") (class "Default")
      (node (ref "D11") (pin "1") (pinfunction "C_1") (pintype "passive"))
      (node (ref "Q38") (pin "3") (pinfunction "E_3") (pintype "passive"))
    )
    (net (code "43") (name "Net-(Q39-E)") (class "Default")
      (node (ref "D12") (pin "1") (pinfunction "C_1") (pintype "passive"))
      (node (ref "Q39") (pin "3") (pinfunction "E_3") (pintype "passive"))
    )
    (net (code "44") (name "Net-(Q40-E)") (class "Default")
      (node (ref "D13") (pin "3") (pinfunction "C_3") (pintype "passive"))
      (node (ref "Q40") (pin "3") (pinfunction "E_3") (pintype "passive"))
    )
    (net (code "45") (name "Net-(Q41-E)") (class "Default")
      (node (ref "D13") (pin "2") (pinfunction "C_2") (pintype "passive"))
      (node (ref "Q41") (pin "3") (pinfunction "E_3") (pintype "passive"))
    )
    (net (code "46") (name "Net-(Q42-E)") (class "Default")
      (node (ref "D13") (pin "1") (pinfunction "C_1") (pintype "passive"))
      (node (ref "Q42") (pin "3") (pinfunction "E_3") (pintype "passive"))
    )
    (net (code "47") (name "Net-(Q43-E)") (class "Default")
      (node (ref "D14") (pin "3") (pinfunction "C_3") (pintype "passive"))
      (node (ref "Q43") (pin "3") (pinfunction "E_3") (pintype "passive"))
    )
    (net (code "48") (name "Net-(Q44-E)") (class "Default")
      (node (ref "D14") (pin "2") (pinfunction "C_2") (pintype "passive"))
      (node (ref "Q44") (pin "3") (pinfunction "E_3") (pintype "passive"))
    )
    (net (code "49") (name "Net-(Q45-E)") (class "Default")
      (node (ref "D14") (pin "1") (pinfunction "C_1") (pintype "passive"))
      (node (ref "Q45") (pin "3") (pinfunction "E_3") (pintype "passive"))
    )
    (net (code "50") (name "Net-(Q46-E)") (class "Default")
      (node (ref "D15") (pin "3") (pinfunction "C_3") (pintype "passive"))
      (node (ref "Q46") (pin "3") (pinfunction "E_3") (pintype "passive"))
    )
    (net (code "51") (name "Net-(Q47-E)") (class "Default")
      (node (ref "D15") (pin "2") (pinfunction "C_2") (pintype "passive"))
      (node (ref "Q47") (pin "3") (pinfunction "E_3") (pintype "passive"))
    )
    (net (code "52") (name "Net-(Q48-E)") (class "Default")
      (node (ref "D15") (pin "1") (pinfunction "C_1") (pintype "passive"))
      (node (ref "Q48") (pin "3") (pinfunction "E_3") (pintype "passive"))
    )
    (net (code "53") (name "Net-(Q49-E)") (class "Default")
      (node (ref "D16") (pin "3") (pinfunction "C_3") (pintype "passive"))
      (node (ref "Q49") (pin "3") (pinfunction "E_3") (pintype "passive"))
    )
    (net (code "54") (name "Net-(Q50-E)") (class "Default")
      (node (ref "D17") (pin "3") (pinfunction "C_3") (pintype "passive"))
      (node (ref "Q50") (pin "3") (pinfunction "E_3") (pintype "passive"))
    )
    (net (code "55") (name "Net-(Q51-E)") (class "Default")
      (node (ref "D18") (pin "3") (pinfunction "C_3") (pintype "passive"))
      (node (ref "Q51") (pin "3") (pinfunction "E_3") (pintype "passive"))
    )
    (net (code "56") (name "Net-(Q52-E)") (class "Default")
      (node (ref "D19") (pin "3") (pinfunction "C_3") (pintype "passive"))
      (node (ref "Q52") (pin "3") (pinfunction "E_3") (pintype "passive"))
    )
    (net (code "57") (name "Net-(Q53-E)") (class "Default")
      (node (ref "D20") (pin "3") (pinfunction "C_3") (pintype "passive"))
      (node (ref "Q53") (pin "3") (pinfunction "E_3") (pintype "passive"))
    )
    (net (code "58") (name "Net-(Q54-E)") (class "Default")
      (node (ref "D16") (pin "2") (pinfunction "C_2") (pintype "passive"))
      (node (ref "Q54") (pin "3") (pinfunction "E_3") (pintype "passive"))
    )
    (net (code "59") (name "Net-(Q55-E)") (class "Default")
      (node (ref "D17") (pin "2") (pinfunction "C_2") (pintype "passive"))
      (node (ref "Q55") (pin "3") (pinfunction "E_3") (pintype "passive"))
    )
    (net (code "60") (name "Net-(Q56-E)") (class "Default")
      (node (ref "D18") (pin "2") (pinfunction "C_2") (pintype "passive"))
      (node (ref "Q56") (pin "3") (pinfunction "E_3") (pintype "passive"))
    )
    (net (code "61") (name "Net-(Q57-E)") (class "Default")
      (node (ref "D19") (pin "2") (pinfunction "C_2") (pintype "passive"))
      (node (ref "Q57") (pin "3") (pinfunction "E_3") (pintype "passive"))
    )
    (net (code "62") (name "Net-(Q58-E)") (class "Default")
      (node (ref "D20") (pin "2") (pinfunction "C_2") (pintype "passive"))
      (node (ref "Q58") (pin "3") (pinfunction "E_3") (pintype "passive"))
    )
    (net (code "63") (name "Net-(Q59-E)") (class "Default")
      (node (ref "D16") (pin "1") (pinfunction "C_1") (pintype "passive"))
      (node (ref "Q59") (pin "3") (pinfunction "E_3") (pintype "passive"))
    )
    (net (code "64") (name "Net-(Q60-E)") (class "Default")
      (node (ref "D17") (pin "1") (pinfunction "C_1") (pintype "passive"))
      (node (ref "Q60") (pin "3") (pinfunction "E_3") (pintype "passive"))
    )
    (net (code "65") (name "Net-(Q61-E)") (class "Default")
      (node (ref "D18") (pin "1") (pinfunction "C_1") (pintype "passive"))
      (node (ref "Q61") (pin "3") (pinfunction "E_3") (pintype "passive"))
    )
    (net (code "66") (name "Net-(Q62-E)") (class "Default")
      (node (ref "D19") (pin "1") (pinfunction "C_1") (pintype "passive"))
      (node (ref "Q62") (pin "3") (pinfunction "E_3") (pintype "passive"))
    )
    (net (code "67") (name "Net-(Q63-E)") (class "Default")
      (node (ref "D20") (pin "1") (pinfunction "C_1") (pintype "passive"))
      (node (ref "Q63") (pin "3") (pinfunction "E_3") (pintype "passive"))
    )
  )
)
